# Boost.net
KiCad netlist of a schematic drawn in Altium Designer
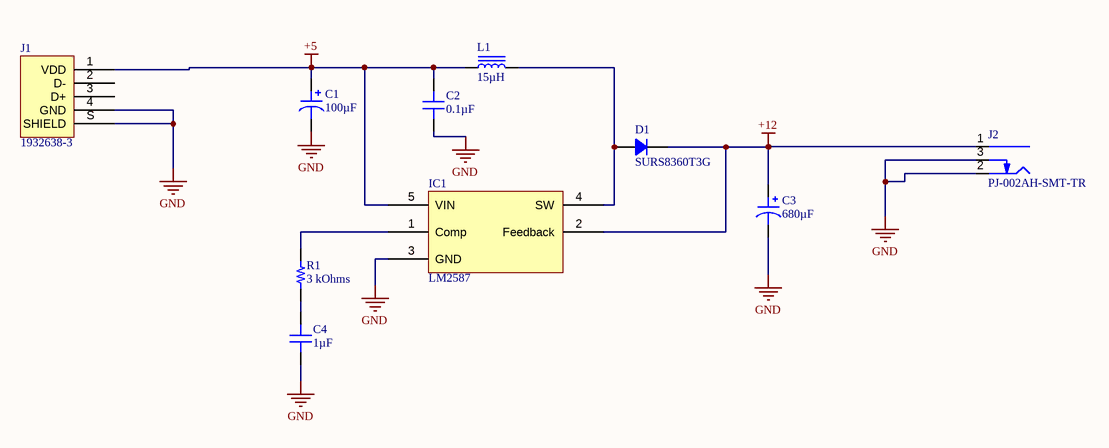
[diagram p0: Boost.SchDoc]

(export (version "E")
  (design (tool "Eeschema 10.0.6"))
  (components
    (comp (ref "C1")
      (value "100µF")
      (footprint "CAP ALSMD 5.3MM H5.4MM")
      (description "CAP ALUM 100UF 20% 10V SMD")
      (fields
        (field (name "PART NUMBER") "EEE-1AA101WR")
        (field (name "MANUFACTURER") "Panasonic Electronic Components")
      )
      (libsource (lib "Celestial Altium Library - altium_library") (part "Polarised Capacitor"))
    )
    (comp (ref "C2")
      (value "0.1µF")
      (footprint "CAP 0805_2012")
      (description "CAP CER 0.1UF 10V X7R 0805")
      (fields (field (name "PART NUMBER") "C0805C104J8RACTU") (field (name "MANUFACTURER") "KEMET"))
      (libsource (lib "Celestial Altium Library - altium_library") (part "Capacitor"))
    )
    (comp (ref "C3")
      (value "680µF")
      (footprint "CAP ALSMD 8.3MM H10.5MM")
      (description "CAP ALUM 680UF 20% 16V SMD")
      (fields
        (field (name "PART NUMBER") "EEE-FT1C681GP")
        (field (name "MANUFACTURER") "Panasonic Electronic Components")
      )
      (libsource (lib "Celestial Altium Library - altium_library") (part "Polarised Capacitor"))
    )
    (comp (ref "C4")
      (value "1µF")
      (footprint "CAP 0805_2012")
      (description "CAP CER 1UF 10V X7R 0805")
      (fields (field (name "PART NUMBER") "MM05ZC105KCZ2A") (field (name "MANUFACTURER") "AVX Corporation"))
      (libsource (lib "Celestial Altium Library - altium_library") (part "Capacitor"))
    )
    (comp (ref "D1")
      (value "SURS8360T3G")
      (footprint "DO214AB SMC")
      (description "DIODE GEN PURP 600V 3A SMC")
      (fields (field (name "MANUFACTURER") "ON Semiconductor"))
      (libsource (lib "Celestial Altium Library - altium_library") (part "Diode"))
    )
    (comp (ref "IC1")
      (value "LM2587")
      (footprint "AltiumLive:D2PAK")
      (description "Boost Converter")
      (libsource (lib "AltiumLive") (part "LM2587"))
    )
    (comp (ref "J1")
      (value "1932638-3")
      (footprint "TE 1932638-3 USB2.0A")
      (description "CONN RCPT USB2.0 TYPEA 4P SMD RA")
      (fields (field (name "MANUFACTURER") "TE Connectivity AMP Connectors"))
      (libsource (lib "Celestial Altium Library - altium_library") (part "TE 1932638-3"))
    )
    (comp (ref "J2")
      (value "PJ-002AH-SMT-TR")
      (footprint "CUI PJ-002AH-SMT-TR")
      (description "CONN PWR JACK 2X5.5MM SOLDER")
      (fields (field (name "MANUFACTURER") "CUI Devices"))
      (libsource (lib "Celestial Altium Library - altium_library") (part "Barrel Connector"))
    )
    (comp (ref "L1")
      (value "15µH")
      (footprint "BOURNS SRR1280")
      (description "FIXED IND 15UH 5.2A 28.5MOHM SMD")
      (fields (field (name "PART NUMBER") "SRR1280-150M") (field (name "MANUFACTURER") "Bourns Inc."))
      (libsource (lib "Celestial Altium Library - altium_library") (part "Inductor"))
    )
    (comp (ref "R1")
      (value "3 kOhms")
      (footprint "RES 0805_2012")
      (description "RES SMD 3K OHM 0.5% 1/8W 0805")
      (fields (field (name "PART NUMBER") "RT0805DRD073KL") (field (name "MANUFACTURER") "Yageo"))
      (libsource (lib "Celestial Altium Library - altium_library") (part "Resistor"))
    )
  )
  (nets
    (net (code "1") (name "+5") (class "Default")
      (node (ref "C1") (pin "1") (pinfunction "1_1") (pintype "passive"))
      (node (ref "C2") (pin "2") (pinfunction "2_2") (pintype "passive"))
      (node (ref "IC1") (pin "5") (pinfunction "VIN_5") (pintype "passive"))
      (node (ref "J1") (pin "1") (pinfunction "VDD_1") (pintype "passive"))
      (node (ref "L1") (pin "1") (pinfunction "1_1") (pintype "passive"))
    )
    (net (code "2") (name "+12") (class "Default")
      (node (ref "C3") (pin "1") (pinfunction "1_1") (pintype "passive"))
      (node (ref "D1") (pin "2") (pinfunction "2_2") (pintype "passive"))
      (node (ref "IC1") (pin "2") (pinfunction "Feedback_2") (pintype "passive"))
      (node (ref "J2") (pin "1") (pinfunction "Centre_1") (pintype "passive"))
    )
    (net (code "3") (name "GND") (class "Default")
      (node (ref "C1") (pin "2") (pinfunction "2_2") (pintype "passive"))
      (node (ref "C2") (pin "1") (pinfunction "1_1") (pintype "passive"))
      (node (ref "C3") (pin "2") (pinfunction "2_2") (pintype "passive"))
      (node (ref "C4") (pin "1") (pinfunction "1_1") (pintype "passive"))
      (node (ref "IC1") (pin "3") (pinfunction "GND_3") (pintype "passive"))
      (node (ref "J1") (pin "4") (pinfunction "GND_4") (pintype "passive"))
      (node (ref "J1") (pin "S") (pinfunction "SHIELD_S") (pintype "passive"))
      (node (ref "J2") (pin "2") (pinfunction "Outer_2") (pintype "passive"))
      (node (ref "J2") (pin "3") (pinfunction "SW_3") (pintype "passive"))
    )
    (net (code "4") (name "Net-(C4-Pad2)") (class "Default")
      (node (ref "C4") (pin "2") (pinfunction "2_2") (pintype "passive"))
      (node (ref "R1") (pin "1") (pinfunction "1_1") (pintype "passive"))
    )
    (net (code "5") (name "Net-(IC1-Comp)") (class "Default")
      (node (ref "IC1") (pin "1") (pinfunction "Comp_1") (pintype "passive"))
      (node (ref "R1") (pin "2") (pinfunction "2_2") (pintype "passive"))
    )
    (net (code "6") (name "Net-(IC1-SW)") (class "Default")
      (node (ref "D1") (pin "1") (pinfunction "1_1") (pintype "passive"))
      (node (ref "IC1") (pin "4") (pinfunction "SW_4") (pintype "passive"))
      (node (ref "L1") (pin "2") (pinfunction "2_2") (pintype "passive"))
    )
    (net (code "7") (name "unconnected-(J1-D+-Pad3)") (class "Default")
      (node (ref "J1") (pin "3") (pinfunction "D+_3") (pintype "passive"))
    )
    (net (code "8") (name "unconnected-(J1-D--Pad2)") (class "Default")
      (node (ref "J1") (pin "2") (pinfunction "D-_2") (pintype "passive"))
    )
  )
)
